# ESP-01-WLED_Shield_-_double_Level_shift0.net
KiCad netlist of a schematic drawn in EAGLE
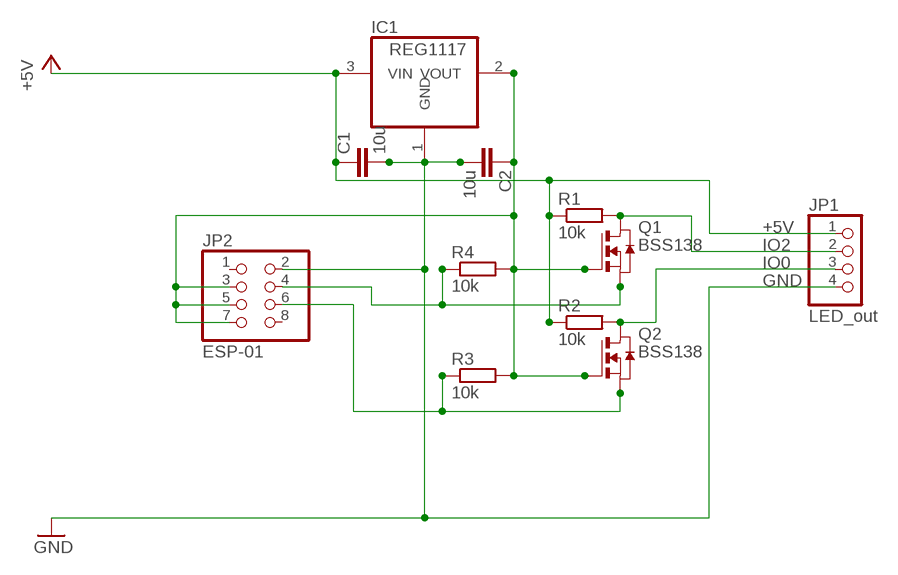
[diagram p0: schematic, sheet 1]

(export (version "E")
  (design (tool "Eeschema 10.0.6"))
  (components
    (comp (ref "C1")
      (value "10u")
      (footprint "eagle-import:C0805K")
      (libsource (lib "eagle-import") (part "C-EUC0805K"))
    )
    (comp (ref "C2")
      (value "10u")
      (footprint "eagle-import:C0805K")
      (libsource (lib "eagle-import") (part "C-EUC0805K"))
    )
    (comp (ref "IC1")
      (value "REG1117")
      (footprint "eagle-import:SOT223")
      (libsource (lib "eagle-import") (part "REG1117"))
    )
    (comp (ref "JP1")
      (value "LED_out")
      (footprint "eagle-import:1X04_90")
      (libsource (lib "eagle-import") (part "PINHD-1X4/90"))
    )
    (comp (ref "JP2")
      (value "ESP-01")
      (footprint "eagle-import:2X04")
      (libsource (lib "eagle-import") (part "PINHD-2X4"))
    )
    (comp (ref "Q1")
      (value "BSS138")
      (footprint "eagle-import:SOT-23")
      (libsource (lib "eagle-import") (part "NMOSSOT23"))
    )
    (comp (ref "Q2")
      (value "BSS138")
      (footprint "eagle-import:SOT-23")
      (libsource (lib "eagle-import") (part "NMOSSOT23"))
    )
    (comp (ref "R1")
      (value "10k")
      (footprint "eagle-import:R0402")
      (libsource (lib "eagle-import") (part "R-EU_R0402"))
    )
    (comp (ref "R2")
      (value "10k")
      (footprint "eagle-import:R0402")
      (libsource (lib "eagle-import") (part "R-EU_R0402"))
    )
    (comp (ref "R3")
      (value "10k")
      (footprint "eagle-import:R0402")
      (libsource (lib "eagle-import") (part "R-EU_R0402"))
    )
    (comp (ref "R4")
      (value "10k")
      (footprint "eagle-import:R0402")
      (libsource (lib "eagle-import") (part "R-EU_R0402"))
    )
  )
  (nets
    (net (code "1") (name "+5V") (class "Default")
      (node (ref "C1") (pin "1") (pinfunction "1_1") (pintype "passive"))
      (node (ref "IC1") (pin "3") (pinfunction "VIN_3") (pintype "input"))
      (node (ref "JP1") (pin "1") (pinfunction "1_1") (pintype "passive"))
      (node (ref "R1") (pin "1") (pinfunction "1_1") (pintype "passive"))
      (node (ref "R2") (pin "1") (pinfunction "1_1") (pintype "passive"))
    )
    (net (code "2") (name "/IO0") (class "Default")
      (node (ref "JP1") (pin "3") (pinfunction "3_3") (pintype "passive"))
      (node (ref "Q2") (pin "1") (pinfunction "D_1") (pintype "passive"))
      (node (ref "R2") (pin "2") (pinfunction "2_2") (pintype "passive"))
    )
    (net (code "3") (name "/IO2") (class "Default")
      (node (ref "JP1") (pin "2") (pinfunction "2_2") (pintype "passive"))
      (node (ref "Q1") (pin "1") (pinfunction "D_1") (pintype "passive"))
      (node (ref "R1") (pin "2") (pinfunction "2_2") (pintype "passive"))
    )
    (net (code "4") (name "GND") (class "Default")
      (node (ref "C1") (pin "2") (pinfunction "2_2") (pintype "passive"))
      (node (ref "C2") (pin "2") (pinfunction "2_2") (pintype "passive"))
      (node (ref "IC1") (pin "1") (pinfunction "GND_1") (pintype "power_in"))
      (node (ref "JP1") (pin "4") (pinfunction "4_4") (pintype "passive"))
      (node (ref "JP2") (pin "2") (pinfunction "2_2") (pintype "passive"))
    )
    (net (code "5") (name "Net-(IC1-VOUT)") (class "Default")
      (node (ref "C2") (pin "1") (pinfunction "1_1") (pintype "passive"))
      (node (ref "IC1") (pin "2") (pinfunction "VOUT_2") (pintype "output"))
      (node (ref "JP2") (pin "3") (pinfunction "3_3") (pintype "passive"))
      (node (ref "JP2") (pin "5") (pinfunction "5_5") (pintype "passive"))
      (node (ref "JP2") (pin "7") (pinfunction "7_7") (pintype "passive"))
      (node (ref "Q1") (pin "3") (pinfunction "G_3") (pintype "passive"))
      (node (ref "Q2") (pin "3") (pinfunction "G_3") (pintype "passive"))
      (node (ref "R3") (pin "2") (pinfunction "2_2") (pintype "passive"))
      (node (ref "R4") (pin "2") (pinfunction "2_2") (pintype "passive"))
    )
    (net (code "6") (name "Net-(Q1-S)") (class "Default")
      (node (ref "JP2") (pin "4") (pinfunction "4_4") (pintype "passive"))
      (node (ref "Q1") (pin "2") (pinfunction "S_2") (pintype "passive"))
      (node (ref "R4") (pin "1") (pinfunction "1_1") (pintype "passive"))
    )
    (net (code "7") (name "Net-(Q2-S)") (class "Default")
      (node (ref "JP2") (pin "6") (pinfunction "6_6") (pintype "passive"))
      (node (ref "Q2") (pin "2") (pinfunction "S_2") (pintype "passive"))
      (node (ref "R3") (pin "1") (pinfunction "1_1") (pintype "passive"))
    )
    (net (code "8") (name "unconnected-(JP2-Pad1)") (class "Default")
      (node (ref "JP2") (pin "1") (pinfunction "1_1") (pintype "passive"))
    )
    (net (code "9") (name "unconnected-(JP2-Pad8)") (class "Default")
      (node (ref "JP2") (pin "8") (pinfunction "8_8") (pintype "passive"))
    )
  )
)
